# MXRDist_1590a.net
KiCad netlist of a schematic drawn in EAGLE
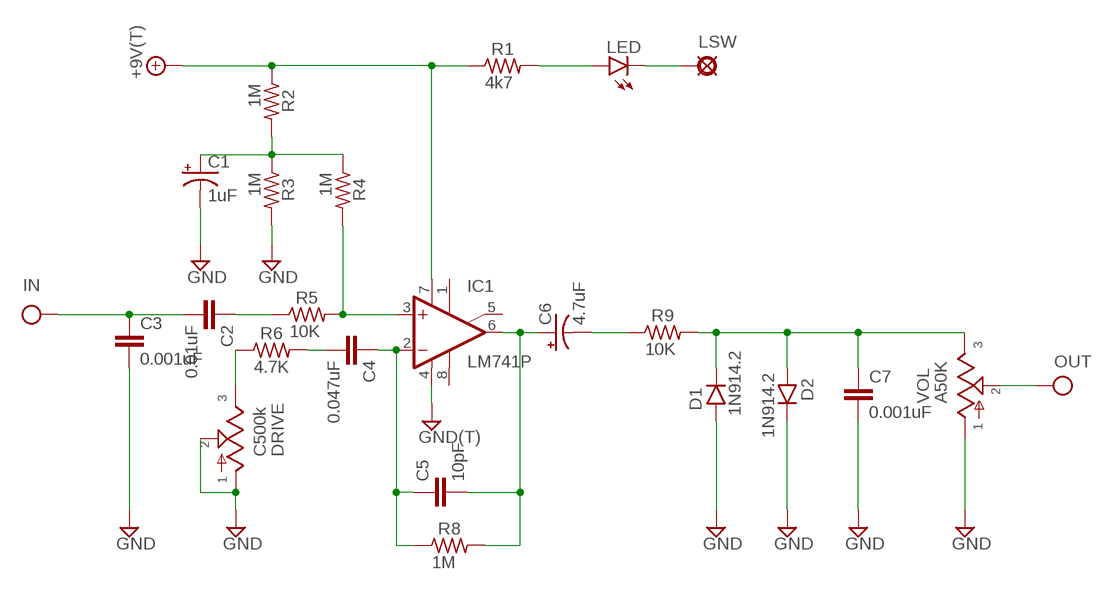
[diagram p0: schematic, sheet 1]

(export (version "E")
  (design (tool "Eeschema 10.0.6"))
  (components
    (comp (ref "+9V")
      (value "+9V(T)")
      (footprint "eagle-import:SQUARE")
      (libsource (lib "eagle-import") (part "+9V(T)"))
    )
    (comp (ref "C1")
      (value "1uF")
      (footprint "eagle-import:044A")
      (libsource (lib "eagle-import") (part "044A1"))
    )
    (comp (ref "C2")
      (value "0.01uF")
      (footprint "eagle-import:070X030")
      (libsource (lib "eagle-import") (part "070X0302"))
    )
    (comp (ref "C3")
      (value "0.001uF")
      (footprint "eagle-import:070X030")
      (libsource (lib "eagle-import") (part "070X0302"))
    )
    (comp (ref "C4")
      (value "0.047uF")
      (footprint "eagle-import:070X030")
      (libsource (lib "eagle-import") (part "070X0302"))
    )
    (comp (ref "C5")
      (value "10pF")
      (footprint "eagle-import:050X030_050_1")
      (libsource (lib "eagle-import") (part "050X030_0501"))
    )
    (comp (ref "C6")
      (value "4.7uF")
      (footprint "eagle-import:044A")
      (libsource (lib "eagle-import") (part "044A1"))
    )
    (comp (ref "C7")
      (value "0.001uF")
      (footprint "eagle-import:070X030")
      (libsource (lib "eagle-import") (part "070X0302"))
    )
    (comp (ref "D1")
      (value "1N914.2")
      (footprint "eagle-import:DO35-2")
      (libsource (lib "eagle-import") (part "1N914.2"))
    )
    (comp (ref "D2")
      (value "1N914.2")
      (footprint "eagle-import:DO35-2")
      (libsource (lib "eagle-import") (part "1N914.2"))
    )
    (comp (ref "DRIVE")
      (value "C500k")
      (footprint "eagle-import:POT_9MM_PACK")
      (libsource (lib "eagle-import") (part "9MM"))
    )
    (comp (ref "GND")
      (value "GND(T)")
      (footprint "eagle-import:SQUARE")
      (libsource (lib "eagle-import") (part "GND(T)"))
    )
    (comp (ref "IC1")
      (value "LM741P")
      (footprint "eagle-import:DIL08")
      (libsource (lib "eagle-import") (part "741PLM"))
    )
    (comp (ref "IN")
      (value "IN(T)")
      (footprint "eagle-import:SQUARE")
      (libsource (lib "eagle-import") (part "IN(T)"))
    )
    (comp (ref "LED")
      (value "LED3MM")
      (footprint "eagle-import:LED3MM")
      (libsource (lib "eagle-import") (part "LED3MM"))
    )
    (comp (ref "LSW")
      (value "PAD")
      (footprint "eagle-import:SQUARE")
      (libsource (lib "eagle-import") (part "PAD"))
    )
    (comp (ref "OUT")
      (value "OUT(T)")
      (footprint "eagle-import:SQUARE")
      (libsource (lib "eagle-import") (part "OUT(T)"))
    )
    (comp (ref "R1")
      (value "4k7")
      (footprint "eagle-import:R0207_1V")
      (libsource (lib "eagle-import") (part "6MM.1"))
    )
    (comp (ref "R2")
      (value "1M")
      (footprint "eagle-import:R0207_1V")
      (libsource (lib "eagle-import") (part "6MM.1"))
    )
    (comp (ref "R3")
      (value "1M")
      (footprint "eagle-import:R0207_1V")
      (libsource (lib "eagle-import") (part "6MM.1"))
    )
    (comp (ref "R4")
      (value "1M")
      (footprint "eagle-import:R0207_1V")
      (libsource (lib "eagle-import") (part "6MM.1"))
    )
    (comp (ref "R5")
      (value "10K")
      (footprint "eagle-import:R0207_1V")
      (libsource (lib "eagle-import") (part "6MM.1"))
    )
    (comp (ref "R6")
      (value "4.7K")
      (footprint "eagle-import:R0207_1V")
      (libsource (lib "eagle-import") (part "6MM.1"))
    )
    (comp (ref "R8")
      (value "1M")
      (footprint "eagle-import:R0207_1V")
      (libsource (lib "eagle-import") (part "6MM.1"))
    )
    (comp (ref "R9")
      (value "10K")
      (footprint "eagle-import:R0207_1V")
      (libsource (lib "eagle-import") (part "6MM.1"))
    )
    (comp (ref "VOL")
      (value "A50K")
      (footprint "eagle-import:POT_9MM_PACK")
      (libsource (lib "eagle-import") (part "9MM"))
    )
  )
  (nets
    (net (code "1") (name "+9V(T)") (class "Default")
      (node (ref "+9V") (pin "1") (pinfunction "+9V_1") (pintype "power_in"))
      (node (ref "IC1") (pin "7") (pinfunction "V+_7") (pintype "power_in"))
      (node (ref "R1") (pin "1") (pinfunction "1_1") (pintype "passive"))
      (node (ref "R2") (pin "1") (pinfunction "1_1") (pintype "passive"))
    )
    (net (code "2") (name "GND") (class "Default")
      (node (ref "C1") (pin "2") (pinfunction "-_2") (pintype "passive"))
      (node (ref "C3") (pin "2") (pinfunction "2_2") (pintype "passive"))
      (node (ref "C7") (pin "2") (pinfunction "2_2") (pintype "passive"))
      (node (ref "D1") (pin "A") (pinfunction "A_A") (pintype "passive"))
      (node (ref "D2") (pin "C") (pinfunction "C_C") (pintype "passive"))
      (node (ref "DRIVE") (pin "P$1") (pinfunction "P$1_P$1") (pintype "bidirectional"))
      (node (ref "DRIVE") (pin "P$2") (pinfunction "P$2_P$2") (pintype "bidirectional"))
      (node (ref "GND") (pin "1") (pinfunction "GND_1") (pintype "power_in"))
      (node (ref "IC1") (pin "4") (pinfunction "V-_4") (pintype "power_in"))
      (node (ref "R3") (pin "2") (pinfunction "2_2") (pintype "passive"))
      (node (ref "VOL") (pin "P$1") (pinfunction "P$1_P$1") (pintype "bidirectional"))
    )
    (net (code "3") (name "IN(T)") (class "Default")
      (node (ref "C2") (pin "2") (pinfunction "2_2") (pintype "passive"))
      (node (ref "C3") (pin "1") (pinfunction "1_1") (pintype "passive"))
      (node (ref "IN") (pin "1") (pinfunction "IN_1") (pintype "power_in"))
    )
    (net (code "4") (name "Net-(C1-+)") (class "Default")
      (node (ref "C1") (pin "1") (pinfunction "+_1") (pintype "passive"))
      (node (ref "R2") (pin "2") (pinfunction "2_2") (pintype "passive"))
      (node (ref "R3") (pin "1") (pinfunction "1_1") (pintype "passive"))
      (node (ref "R4") (pin "1") (pinfunction "1_1") (pintype "passive"))
    )
    (net (code "5") (name "Net-(C2-Pad1)") (class "Default")
      (node (ref "C2") (pin "1") (pinfunction "1_1") (pintype "passive"))
      (node (ref "R5") (pin "1") (pinfunction "1_1") (pintype "passive"))
    )
    (net (code "6") (name "Net-(C4-Pad2)") (class "Default")
      (node (ref "C4") (pin "2") (pinfunction "2_2") (pintype "passive"))
      (node (ref "R6") (pin "2") (pinfunction "2_2") (pintype "passive"))
    )
    (net (code "7") (name "Net-(C6-+)") (class "Default")
      (node (ref "C5") (pin "2") (pinfunction "2_2") (pintype "passive"))
      (node (ref "C6") (pin "1") (pinfunction "+_1") (pintype "passive"))
      (node (ref "IC1") (pin "6") (pinfunction "OUT_6") (pintype "output"))
      (node (ref "R8") (pin "2") (pinfunction "2_2") (pintype "passive"))
    )
    (net (code "8") (name "Net-(C6--)") (class "Default")
      (node (ref "C6") (pin "2") (pinfunction "-_2") (pintype "passive"))
      (node (ref "R9") (pin "1") (pinfunction "1_1") (pintype "passive"))
    )
    (net (code "9") (name "Net-(C7-Pad1)") (class "Default")
      (node (ref "C7") (pin "1") (pinfunction "1_1") (pintype "passive"))
      (node (ref "D1") (pin "C") (pinfunction "C_C") (pintype "passive"))
      (node (ref "D2") (pin "A") (pinfunction "A_A") (pintype "passive"))
      (node (ref "R9") (pin "2") (pinfunction "2_2") (pintype "passive"))
      (node (ref "VOL") (pin "P$3") (pinfunction "P$3_P$3") (pintype "bidirectional"))
    )
    (net (code "10") (name "Net-(DRIVE-PadP$3)") (class "Default")
      (node (ref "DRIVE") (pin "P$3") (pinfunction "P$3_P$3") (pintype "bidirectional"))
      (node (ref "R6") (pin "1") (pinfunction "1_1") (pintype "passive"))
    )
    (net (code "11") (name "Net-(IC1-+IN)") (class "Default")
      (node (ref "IC1") (pin "3") (pinfunction "+IN_3") (pintype "input"))
      (node (ref "R4") (pin "2") (pinfunction "2_2") (pintype "passive"))
      (node (ref "R5") (pin "2") (pinfunction "2_2") (pintype "passive"))
    )
    (net (code "12") (name "Net-(IC1--IN)") (class "Default")
      (node (ref "C4") (pin "1") (pinfunction "1_1") (pintype "passive"))
      (node (ref "C5") (pin "1") (pinfunction "1_1") (pintype "passive"))
      (node (ref "IC1") (pin "2") (pinfunction "-IN_2") (pintype "input"))
      (node (ref "R8") (pin "1") (pinfunction "1_1") (pintype "passive"))
    )
    (net (code "13") (name "Net-(LED-C)") (class "Default")
      (node (ref "LED") (pin "K") (pinfunction "C_K") (pintype "passive"))
      (node (ref "LSW") (pin "1") (pinfunction "PAD_1") (pintype "passive"))
    )
    (net (code "14") (name "Net-(LED-PadA)") (class "Default")
      (node (ref "LED") (pin "A") (pinfunction "A_A") (pintype "passive"))
      (node (ref "R1") (pin "2") (pinfunction "2_2") (pintype "passive"))
    )
    (net (code "15") (name "OUT(T)") (class "Default")
      (node (ref "OUT") (pin "1") (pinfunction "OUT_1") (pintype "power_in"))
      (node (ref "VOL") (pin "P$2") (pinfunction "P$2_P$2") (pintype "bidirectional"))
    )
    (net (code "16") (name "unconnected-(IC1-ON1-Pad1)") (class "Default")
      (node (ref "IC1") (pin "1") (pinfunction "ON1_1") (pintype "passive"))
    )
    (net (code "17") (name "unconnected-(IC1-ON2-Pad5)") (class "Default")
      (node (ref "IC1") (pin "5") (pinfunction "ON2_5") (pintype "passive"))
    )
    (net (code "18") (name "unconnected-(IC1-OPT-Pad8)") (class "Default")
      (node (ref "IC1") (pin "8") (pinfunction "OPT_8") (pintype "passive"))
    )
  )
)
